# integrator.net
KiCad netlist of a schematic drawn in EAGLE
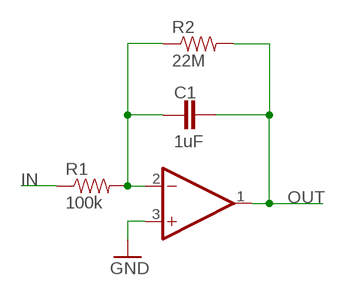
[diagram p0: schematic, sheet 1]

(export (version "E")
  (design (tool "Eeschema 10.0.6"))
  (components
    (comp (ref "C1")
      (value "1uF")
      (footprint "eagle-import:0402-CAP")
      (libsource (lib "eagle-import") (part "CAP0402-CAP"))
    )
    (comp (ref "IC1")
      (value "MCP6022")
      (footprint "eagle-import:SOIC8_150MIL")
      (libsource (lib "eagle-import") (part "MCP6022"))
    )
    (comp (ref "R1")
      (value "100k")
      (footprint "eagle-import:0402-RES")
      (libsource (lib "eagle-import") (part "RESISTOR0402-RES"))
    )
    (comp (ref "R2")
      (value "22M")
      (footprint "eagle-import:0402-RES")
      (libsource (lib "eagle-import") (part "RESISTOR0402-RES"))
    )
  )
  (nets
    (net (code "1") (name "/IN") (class "Default")
      (node (ref "R1") (pin "1") (pinfunction "1_1") (pintype "passive"))
    )
    (net (code "2") (name "/OUT") (class "Default")
      (node (ref "C1") (pin "2") (pinfunction "2_2") (pintype "passive"))
      (node (ref "IC1") (pin "1") (pinfunction "OUT_1") (pintype "output"))
      (node (ref "R2") (pin "2") (pinfunction "2_2") (pintype "passive"))
    )
    (net (code "3") (name "GND") (class "Default")
      (node (ref "IC1") (pin "3") (pinfunction "+IN_3") (pintype "input"))
    )
    (net (code "4") (name "Net-(IC1A--IN)") (class "Default")
      (node (ref "C1") (pin "1") (pinfunction "1_1") (pintype "passive"))
      (node (ref "IC1") (pin "2") (pinfunction "-IN_2") (pintype "input"))
      (node (ref "R1") (pin "2") (pinfunction "2_2") (pintype "passive"))
      (node (ref "R2") (pin "1") (pinfunction "1_1") (pintype "passive"))
    )
  )
)
